# 5_-OPI_MAIN.net
KiCad netlist of a schematic drawn in Altium Designer
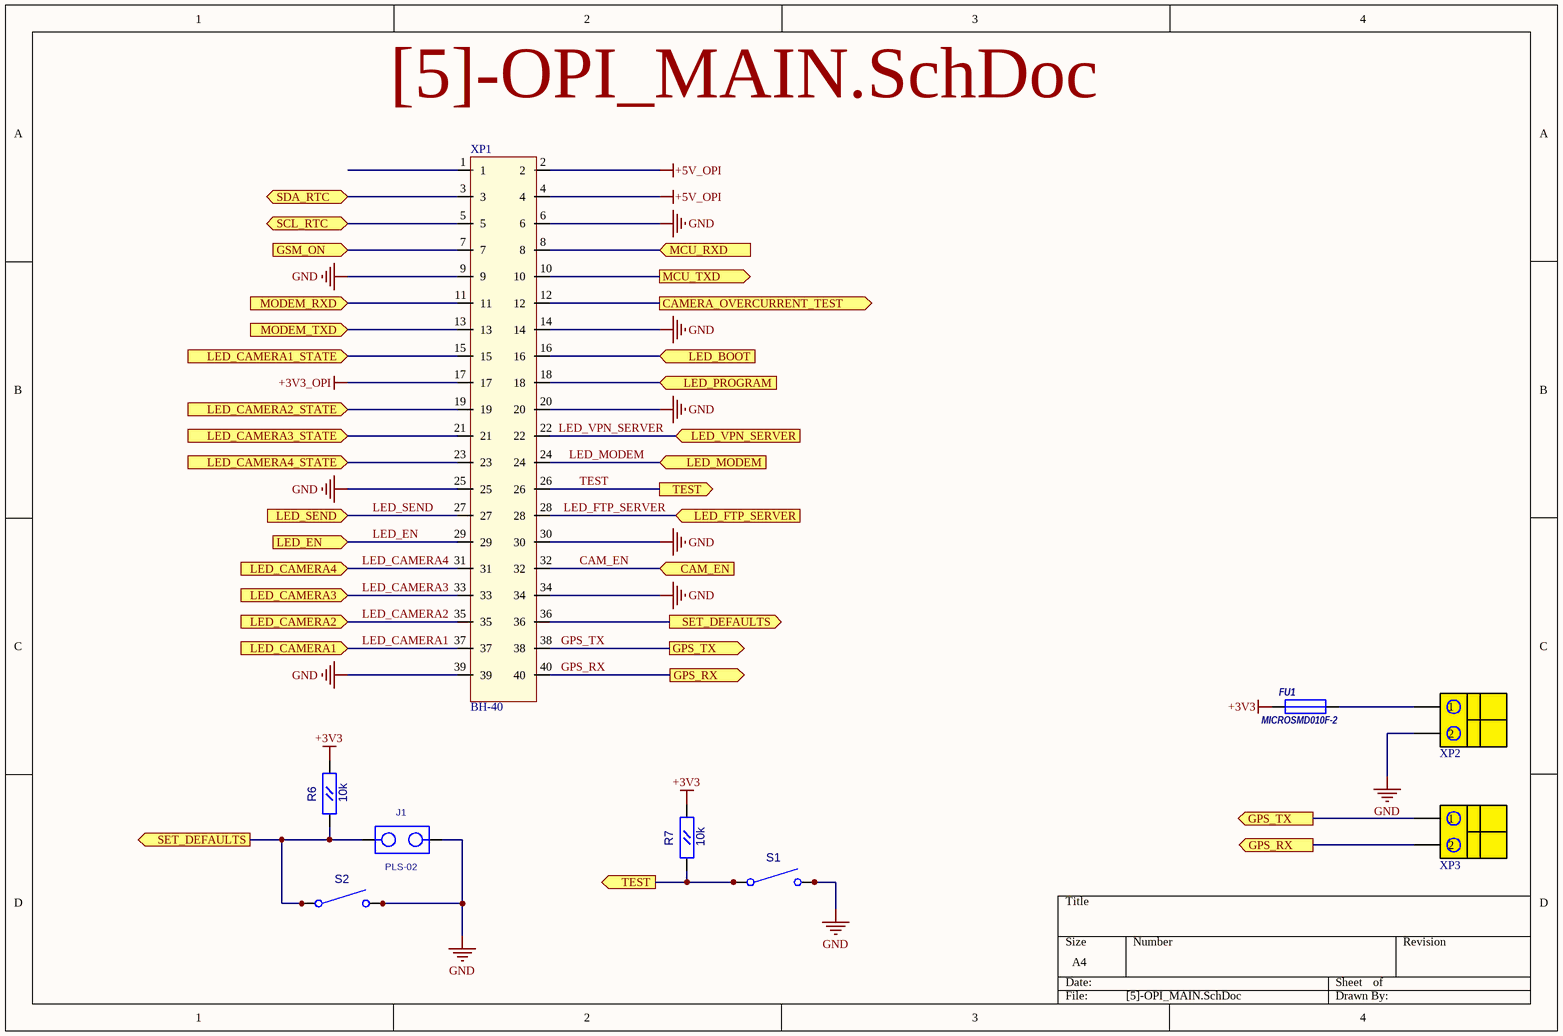
[diagram p0: [5]-OPI_MAIN.SchDoc]

(export (version "E")
  (design (tool "Eeschema 10.0.6"))
  (components
    (comp (ref "FU1")
      (value "MICROSMD010F-2")
      (footprint "RC1210")
      (description "MICROSMD")
      (libsource (lib "fizik_lib") (part "MICROSMD"))
    )
    (comp (ref "J1") (value "PLS-02") (footprint "PLS-02") (libsource (lib "fizik_lib") (part "PLS-02")))
    (comp (ref "R6")
      (value "10k")
      (footprint "RC0603")
      (description "RC0603")
      (libsource (lib "fizik_lib") (part "RC0603"))
    )
    (comp (ref "R7")
      (value "10k")
      (footprint "RC0603")
      (description "RC0603")
      (libsource (lib "fizik_lib") (part "RC0603"))
    )
    (comp (ref "S1")
      (value "DTSM-61N")
      (footprint "DTSM-61N")
      (description "Switch, Single Pole, Single Throw, Normally Open")
      (libsource (lib "fizik_lib") (part "DTSM-61N"))
    )
    (comp (ref "S2")
      (value "DTSM-61N")
      (footprint "DTSM-61N")
      (description "Switch, Single Pole, Single Throw, Normally Open")
      (libsource (lib "fizik_lib") (part "DTSM-61N"))
    )
    (comp (ref "XP1")
      (value "BH-40")
      (footprint "BH-40")
      (description "2.54mm connector with key")
      (libsource (lib "fizik_lib") (part "BH-40"))
    )
    (comp (ref "XP2")
      (value "DG330-2P")
      (footprint "DG330-2P")
      (description "Degson 2 pin connector rear")
      (libsource (lib "fizik_lib") (part "DG330-2P"))
    )
    (comp (ref "XP3")
      (value "DG330-2P")
      (footprint "DG330-2P")
      (description "Degson 2 pin connector rear")
      (libsource (lib "fizik_lib") (part "DG330-2P"))
    )
  )
  (nets
    (net (code "1") (name "+3V3") (class "Default")
      (node (ref "FU1") (pin "1") (pintype "passive"))
      (node (ref "R6") (pin "2") (pinfunction "B_2") (pintype "passive"))
      (node (ref "R7") (pin "2") (pinfunction "B_2") (pintype "passive"))
    )
    (net (code "2") (name "+3V3_OPI") (class "Default")
      (node (ref "XP1") (pin "17") (pinfunction "17_17") (pintype "passive"))
    )
    (net (code "3") (name "+5V_OPI") (class "Default")
      (node (ref "XP1") (pin "2") (pinfunction "2_2") (pintype "passive"))
      (node (ref "XP1") (pin "4") (pinfunction "4_4") (pintype "passive"))
    )
    (net (code "4") (name "/CAMERA_OVERCURRENT_TEST") (class "Default")
      (node (ref "XP1") (pin "12") (pinfunction "12_12") (pintype "passive"))
    )
    (net (code "5") (name "/CAM_EN") (class "Default")
      (node (ref "XP1") (pin "32") (pinfunction "32_32") (pintype "passive"))
    )
    (net (code "6") (name "/GPS_RX") (class "Default")
      (node (ref "XP1") (pin "40") (pinfunction "40_40") (pintype "passive"))
      (node (ref "XP3") (pin "2") (pinfunction "2_2") (pintype "passive"))
    )
    (net (code "7") (name "/GPS_TX") (class "Default")
      (node (ref "XP1") (pin "38") (pinfunction "38_38") (pintype "passive"))
      (node (ref "XP3") (pin "1") (pinfunction "1_1") (pintype "passive"))
    )
    (net (code "8") (name "/GSM_ON") (class "Default")
      (node (ref "XP1") (pin "7") (pinfunction "7_7") (pintype "passive"))
    )
    (net (code "9") (name "/LED_BOOT") (class "Default")
      (node (ref "XP1") (pin "16") (pinfunction "16_16") (pintype "passive"))
    )
    (net (code "10") (name "/LED_CAMERA1") (class "Default")
      (node (ref "XP1") (pin "37") (pinfunction "37_37") (pintype "passive"))
    )
    (net (code "11") (name "/LED_CAMERA1_STATE") (class "Default")
      (node (ref "XP1") (pin "15") (pinfunction "15_15") (pintype "passive"))
    )
    (net (code "12") (name "/LED_CAMERA2") (class "Default")
      (node (ref "XP1") (pin "35") (pinfunction "35_35") (pintype "passive"))
    )
    (net (code "13") (name "/LED_CAMERA2_STATE") (class "Default")
      (node (ref "XP1") (pin "19") (pinfunction "19_19") (pintype "passive"))
    )
    (net (code "14") (name "/LED_CAMERA3") (class "Default")
      (node (ref "XP1") (pin "33") (pinfunction "33_33") (pintype "passive"))
    )
    (net (code "15") (name "/LED_CAMERA3_STATE") (class "Default")
      (node (ref "XP1") (pin "21") (pinfunction "21_21") (pintype "passive"))
    )
    (net (code "16") (name "/LED_CAMERA4") (class "Default")
      (node (ref "XP1") (pin "31") (pinfunction "31_31") (pintype "passive"))
    )
    (net (code "17") (name "/LED_CAMERA4_STATE") (class "Default")
      (node (ref "XP1") (pin "23") (pinfunction "23_23") (pintype "passive"))
    )
    (net (code "18") (name "/LED_EN") (class "Default")
      (node (ref "XP1") (pin "29") (pinfunction "29_29") (pintype "passive"))
    )
    (net (code "19") (name "/LED_FTP_SERVER") (class "Default")
      (node (ref "XP1") (pin "28") (pinfunction "28_28") (pintype "passive"))
    )
    (net (code "20") (name "/LED_MODEM") (class "Default")
      (node (ref "XP1") (pin "24") (pinfunction "24_24") (pintype "passive"))
    )
    (net (code "21") (name "/LED_PROGRAM") (class "Default")
      (node (ref "XP1") (pin "18") (pinfunction "18_18") (pintype "passive"))
    )
    (net (code "22") (name "/LED_SEND") (class "Default")
      (node (ref "XP1") (pin "27") (pinfunction "27_27") (pintype "passive"))
    )
    (net (code "23") (name "/LED_VPN_SERVER") (class "Default")
      (node (ref "XP1") (pin "22") (pinfunction "22_22") (pintype "passive"))
    )
    (net (code "24") (name "/MCU_RXD") (class "Default")
      (node (ref "XP1") (pin "8") (pinfunction "8_8") (pintype "passive"))
    )
    (net (code "25") (name "/MCU_TXD") (class "Default")
      (node (ref "XP1") (pin "10") (pinfunction "10_10") (pintype "passive"))
    )
    (net (code "26") (name "/MODEM_RXD") (class "Default")
      (node (ref "XP1") (pin "11") (pinfunction "11_11") (pintype "passive"))
    )
    (net (code "27") (name "/MODEM_TXD") (class "Default")
      (node (ref "XP1") (pin "13") (pinfunction "13_13") (pintype "passive"))
    )
    (net (code "28") (name "/SCL_RTC") (class "Default")
      (node (ref "XP1") (pin "5") (pinfunction "5_5") (pintype "passive"))
    )
    (net (code "29") (name "/SDA_RTC") (class "Default")
      (node (ref "XP1") (pin "3") (pinfunction "3_3") (pintype "passive"))
    )
    (net (code "30") (name "/SET_DEFAULTS") (class "Default")
      (node (ref "J1") (pin "1") (pintype "passive"))
      (node (ref "R6") (pin "1") (pinfunction "A_1") (pintype "passive"))
      (node (ref "S2") (pin "1") (pinfunction "C1_1") (pintype "passive"))
      (node (ref "S2") (pin "2") (pintype "passive"))
      (node (ref "XP1") (pin "36") (pinfunction "36_36") (pintype "passive"))
    )
    (net (code "31") (name "/TEST") (class "Default")
      (node (ref "R7") (pin "1") (pinfunction "A_1") (pintype "passive"))
      (node (ref "S1") (pin "1") (pinfunction "C1_1") (pintype "passive"))
      (node (ref "S1") (pin "2") (pintype "passive"))
      (node (ref "XP1") (pin "26") (pinfunction "26_26") (pintype "passive"))
    )
    (net (code "32") (name "GND") (class "Default")
      (node (ref "J1") (pin "2") (pintype "passive"))
      (node (ref "S1") (pin "3") (pinfunction "C2_3") (pintype "passive"))
      (node (ref "S1") (pin "4") (pintype "passive"))
      (node (ref "S2") (pin "3") (pinfunction "C2_3") (pintype "passive"))
      (node (ref "S2") (pin "4") (pintype "passive"))
      (node (ref "XP1") (pin "14") (pinfunction "14_14") (pintype "passive"))
      (node (ref "XP1") (pin "20") (pinfunction "20_20") (pintype "passive"))
      (node (ref "XP1") (pin "25") (pinfunction "25_25") (pintype "passive"))
      (node (ref "XP1") (pin "30") (pinfunction "30_30") (pintype "passive"))
      (node (ref "XP1") (pin "34") (pinfunction "34_34") (pintype "passive"))
      (node (ref "XP1") (pin "39") (pinfunction "39_39") (pintype "passive"))
      (node (ref "XP1") (pin "6") (pinfunction "6_6") (pintype "passive"))
      (node (ref "XP1") (pin "9") (pinfunction "9_9") (pintype "passive"))
      (node (ref "XP2") (pin "2") (pinfunction "2_2") (pintype "passive"))
    )
    (net (code "33") (name "Net-(FU1-Pad2)") (class "Default")
      (node (ref "FU1") (pin "2") (pintype "passive"))
      (node (ref "XP2") (pin "1") (pinfunction "1_1") (pintype "passive"))
    )
    (net (code "34") (name "unconnected-(XP1-Pad1)") (class "Default")
      (node (ref "XP1") (pin "1") (pinfunction "1_1") (pintype "passive"))
    )
  )
)
